# Arduino_Micro_DRAM_Tester.net
KiCad netlist of a schematic drawn in EAGLE
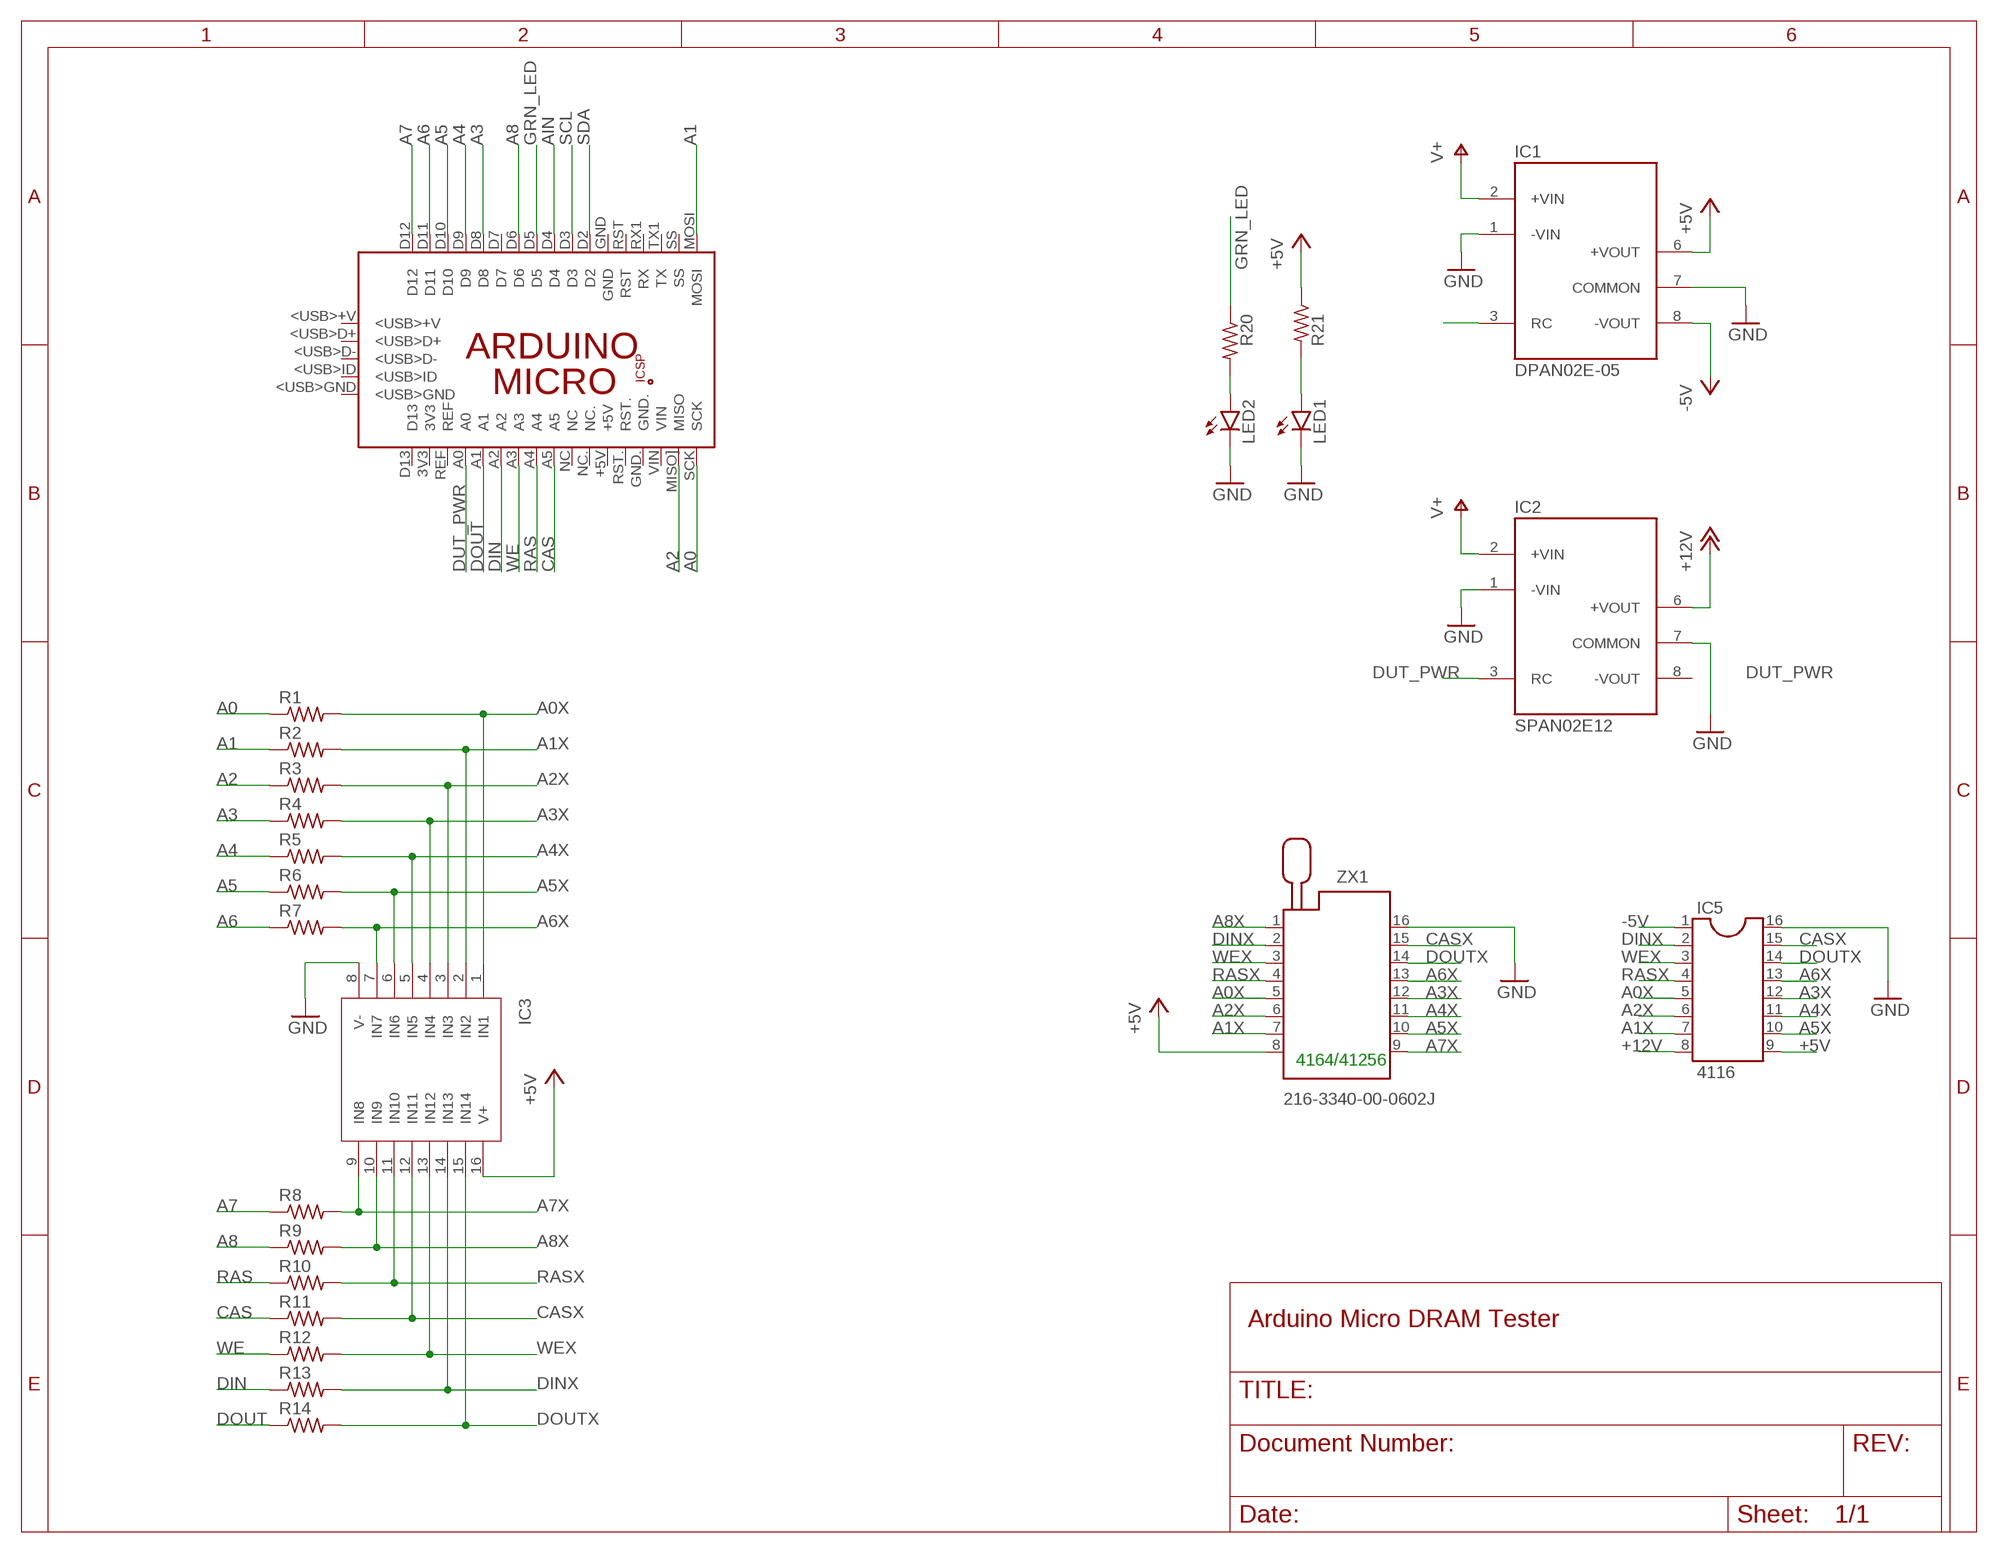
[diagram p0: schematic, sheet 1]

(export (version "E")
  (design (tool "Eeschema 10.0.6"))
  (components
    (comp (ref "IC1")
      (value "DPAN02E-05")
      (footprint "eagle-import:SIP7")
      (libsource (lib "eagle-import") (part "DPAN02"))
    )
    (comp (ref "IC2")
      (value "SPAN02E12")
      (footprint "eagle-import:SIP7")
      (libsource (lib "eagle-import") (part "DPAN02"))
    )
    (comp (ref "IC3")
      (value "SP720")
      (footprint "eagle-import:DIL16")
      (libsource (lib "eagle-import") (part "SP720"))
    )
    (comp (ref "IC5")
      (value "4116")
      (footprint "eagle-import:SOCKET-16")
      (libsource (lib "eagle-import") (part "DIL16S"))
    )
    (comp (ref "LED1")
      (value "LED5MM")
      (footprint "eagle-import:LED5MM")
      (libsource (lib "eagle-import") (part "LED5MM"))
    )
    (comp (ref "LED2")
      (value "LED5MM")
      (footprint "eagle-import:LED5MM")
      (libsource (lib "eagle-import") (part "LED5MM"))
    )
    (comp (ref "PCB1")
      (value "ARDUINO_MICRO")
      (footprint "eagle-import:ARDUINO_MICRO")
      (libsource (lib "eagle-import") (part "ARDUINO_MICRO"))
    )
    (comp (ref "R1")
      (value "R-US_V235/17")
      (footprint "eagle-import:V235_17")
      (libsource (lib "eagle-import") (part "R-US_V235/17"))
    )
    (comp (ref "R2")
      (value "R-US_V235/17")
      (footprint "eagle-import:V235_17")
      (libsource (lib "eagle-import") (part "R-US_V235/17"))
    )
    (comp (ref "R3")
      (value "R-US_V235/17")
      (footprint "eagle-import:V235_17")
      (libsource (lib "eagle-import") (part "R-US_V235/17"))
    )
    (comp (ref "R4")
      (value "R-US_V235/17")
      (footprint "eagle-import:V235_17")
      (libsource (lib "eagle-import") (part "R-US_V235/17"))
    )
    (comp (ref "R5")
      (value "R-US_V235/17")
      (footprint "eagle-import:V235_17")
      (libsource (lib "eagle-import") (part "R-US_V235/17"))
    )
    (comp (ref "R6")
      (value "R-US_V235/17")
      (footprint "eagle-import:V235_17")
      (libsource (lib "eagle-import") (part "R-US_V235/17"))
    )
    (comp (ref "R7")
      (value "R-US_V235/17")
      (footprint "eagle-import:V235_17")
      (libsource (lib "eagle-import") (part "R-US_V235/17"))
    )
    (comp (ref "R8")
      (value "R-US_V235/17")
      (footprint "eagle-import:V235_17")
      (libsource (lib "eagle-import") (part "R-US_V235/17"))
    )
    (comp (ref "R9")
      (value "R-US_V235/17")
      (footprint "eagle-import:V235_17")
      (libsource (lib "eagle-import") (part "R-US_V235/17"))
    )
    (comp (ref "R10")
      (value "R-US_V235/17")
      (footprint "eagle-import:V235_17")
      (libsource (lib "eagle-import") (part "R-US_V235/17"))
    )
    (comp (ref "R11")
      (value "R-US_V235/17")
      (footprint "eagle-import:V235_17")
      (libsource (lib "eagle-import") (part "R-US_V235/17"))
    )
    (comp (ref "R12")
      (value "R-US_V235/17")
      (footprint "eagle-import:V235_17")
      (libsource (lib "eagle-import") (part "R-US_V235/17"))
    )
    (comp (ref "R13")
      (value "R-US_V235/17")
      (footprint "eagle-import:V235_17")
      (libsource (lib "eagle-import") (part "R-US_V235/17"))
    )
    (comp (ref "R14")
      (value "R-US_V235/17")
      (footprint "eagle-import:V235_17")
      (libsource (lib "eagle-import") (part "R-US_V235/17"))
    )
    (comp (ref "R20")
      (value "R-US_0309/10")
      (footprint "eagle-import:0309_10")
      (libsource (lib "eagle-import") (part "resistor_348_R-US_0309/10"))
    )
    (comp (ref "R21")
      (value "R-US_0309/10")
      (footprint "eagle-import:0309_10")
      (libsource (lib "eagle-import") (part "resistor_348_R-US_0309/10"))
    )
    (comp (ref "ZX1")
      (value "216-3340-00-0602J")
      (footprint "eagle-import:216-3340-00-0602J")
      (libsource (lib "eagle-import") (part "216-3340-00-0602J"))
    )
  )
  (nets
    (net (code "1") (name "+5V") (class "Default")
      (node (ref "IC1") (pin "6") (pinfunction "+VOUT_6") (pintype "passive"))
      (node (ref "IC3") (pin "16") (pinfunction "V+_16") (pintype "input"))
      (node (ref "IC5") (pin "9") (pinfunction "9_9") (pintype "passive"))
      (node (ref "R21") (pin "1") (pinfunction "1_1") (pintype "passive"))
      (node (ref "ZX1") (pin "8") (pinfunction "8_8") (pintype "passive"))
    )
    (net (code "2") (name "+12V") (class "Default")
      (node (ref "IC2") (pin "6") (pinfunction "+VOUT_6") (pintype "passive"))
      (node (ref "IC5") (pin "8") (pinfunction "8_8") (pintype "passive"))
    )
    (net (code "3") (name "-5V") (class "Default")
      (node (ref "IC1") (pin "8") (pinfunction "-VOUT_8") (pintype "passive"))
      (node (ref "IC5") (pin "1") (pinfunction "1_1") (pintype "passive"))
    )
    (net (code "4") (name "/A0") (class "Default")
      (node (ref "PCB1") (pin "SCK") (pinfunction "SCK_SCK") (pintype "bidirectional"))
      (node (ref "R1") (pin "1") (pinfunction "1_1") (pintype "passive"))
    )
    (net (code "5") (name "/A0X") (class "Default")
      (node (ref "IC3") (pin "1") (pinfunction "IN1_1") (pintype "input"))
      (node (ref "IC5") (pin "5") (pinfunction "5_5") (pintype "passive"))
      (node (ref "R1") (pin "2") (pinfunction "2_2") (pintype "passive"))
      (node (ref "ZX1") (pin "5") (pinfunction "5_5") (pintype "passive"))
    )
    (net (code "6") (name "/A1") (class "Default")
      (node (ref "PCB1") (pin "MOSI") (pinfunction "MOSI_MOSI") (pintype "bidirectional"))
      (node (ref "R2") (pin "1") (pinfunction "1_1") (pintype "passive"))
    )
    (net (code "7") (name "/A1X") (class "Default")
      (node (ref "IC3") (pin "2") (pinfunction "IN2_2") (pintype "input"))
      (node (ref "IC5") (pin "7") (pinfunction "7_7") (pintype "passive"))
      (node (ref "R2") (pin "2") (pinfunction "2_2") (pintype "passive"))
      (node (ref "ZX1") (pin "7") (pinfunction "7_7") (pintype "passive"))
    )
    (net (code "8") (name "/A2") (class "Default")
      (node (ref "PCB1") (pin "MISO]") (pinfunction "MISO_MISO]") (pintype "bidirectional"))
      (node (ref "R3") (pin "1") (pinfunction "1_1") (pintype "passive"))
    )
    (net (code "9") (name "/A2X") (class "Default")
      (node (ref "IC3") (pin "3") (pinfunction "IN3_3") (pintype "input"))
      (node (ref "IC5") (pin "6") (pinfunction "6_6") (pintype "passive"))
      (node (ref "R3") (pin "2") (pinfunction "2_2") (pintype "passive"))
      (node (ref "ZX1") (pin "6") (pinfunction "6_6") (pintype "passive"))
    )
    (net (code "10") (name "/A3") (class "Default")
      (node (ref "PCB1") (pin "D8") (pinfunction "D8_D8") (pintype "bidirectional"))
      (node (ref "R4") (pin "1") (pinfunction "1_1") (pintype "passive"))
    )
    (net (code "11") (name "/A3X") (class "Default")
      (node (ref "IC3") (pin "4") (pinfunction "IN4_4") (pintype "input"))
      (node (ref "IC5") (pin "12") (pinfunction "12_12") (pintype "passive"))
      (node (ref "R4") (pin "2") (pinfunction "2_2") (pintype "passive"))
      (node (ref "ZX1") (pin "12") (pinfunction "12_12") (pintype "passive"))
    )
    (net (code "12") (name "/A4") (class "Default")
      (node (ref "PCB1") (pin "D9") (pinfunction "D9_D9") (pintype "bidirectional"))
      (node (ref "R5") (pin "1") (pinfunction "1_1") (pintype "passive"))
    )
    (net (code "13") (name "/A4X") (class "Default")
      (node (ref "IC3") (pin "5") (pinfunction "IN5_5") (pintype "input"))
      (node (ref "IC5") (pin "11") (pinfunction "11_11") (pintype "passive"))
      (node (ref "R5") (pin "2") (pinfunction "2_2") (pintype "passive"))
      (node (ref "ZX1") (pin "11") (pinfunction "11_11") (pintype "passive"))
    )
    (net (code "14") (name "/A5") (class "Default")
      (node (ref "PCB1") (pin "D10") (pinfunction "D10_D10") (pintype "bidirectional"))
      (node (ref "R6") (pin "1") (pinfunction "1_1") (pintype "passive"))
    )
    (net (code "15") (name "/A5X") (class "Default")
      (node (ref "IC3") (pin "6") (pinfunction "IN6_6") (pintype "input"))
      (node (ref "IC5") (pin "10") (pinfunction "10_10") (pintype "passive"))
      (node (ref "R6") (pin "2") (pinfunction "2_2") (pintype "passive"))
      (node (ref "ZX1") (pin "10") (pinfunction "10_10") (pintype "passive"))
    )
    (net (code "16") (name "/A6") (class "Default")
      (node (ref "PCB1") (pin "D11") (pinfunction "D11_D11") (pintype "bidirectional"))
      (node (ref "R7") (pin "1") (pinfunction "1_1") (pintype "passive"))
    )
    (net (code "17") (name "/A6X") (class "Default")
      (node (ref "IC3") (pin "7") (pinfunction "IN7_7") (pintype "input"))
      (node (ref "IC5") (pin "13") (pinfunction "13_13") (pintype "passive"))
      (node (ref "R7") (pin "2") (pinfunction "2_2") (pintype "passive"))
      (node (ref "ZX1") (pin "13") (pinfunction "13_13") (pintype "passive"))
    )
    (net (code "18") (name "/A7") (class "Default")
      (node (ref "PCB1") (pin "D12") (pinfunction "D12_D12") (pintype "bidirectional"))
      (node (ref "R8") (pin "1") (pinfunction "1_1") (pintype "passive"))
    )
    (net (code "19") (name "/A7X") (class "Default")
      (node (ref "IC3") (pin "9") (pinfunction "IN8_9") (pintype "input"))
      (node (ref "R8") (pin "2") (pinfunction "2_2") (pintype "passive"))
      (node (ref "ZX1") (pin "9") (pinfunction "9_9") (pintype "passive"))
    )
    (net (code "20") (name "/A8") (class "Default")
      (node (ref "PCB1") (pin "D6") (pinfunction "D6_D6") (pintype "bidirectional"))
      (node (ref "R9") (pin "1") (pinfunction "1_1") (pintype "passive"))
    )
    (net (code "21") (name "/A8X") (class "Default")
      (node (ref "IC3") (pin "10") (pinfunction "IN9_10") (pintype "input"))
      (node (ref "R9") (pin "2") (pinfunction "2_2") (pintype "passive"))
      (node (ref "ZX1") (pin "1") (pinfunction "1_1") (pintype "passive"))
    )
    (net (code "22") (name "/AIN") (class "Default")
      (node (ref "PCB1") (pin "D4") (pinfunction "D4_D4") (pintype "bidirectional"))
    )
    (net (code "23") (name "/CAS") (class "Default")
      (node (ref "PCB1") (pin "A5") (pinfunction "A5_A5") (pintype "bidirectional"))
      (node (ref "R11") (pin "1") (pinfunction "1_1") (pintype "passive"))
    )
    (net (code "24") (name "/CASX") (class "Default")
      (node (ref "IC3") (pin "12") (pinfunction "IN11_12") (pintype "input"))
      (node (ref "IC5") (pin "15") (pinfunction "15_15") (pintype "passive"))
      (node (ref "R11") (pin "2") (pinfunction "2_2") (pintype "passive"))
      (node (ref "ZX1") (pin "15") (pinfunction "15_15") (pintype "passive"))
    )
    (net (code "25") (name "/DIN") (class "Default")
      (node (ref "PCB1") (pin "A2") (pinfunction "A2_A2") (pintype "bidirectional"))
      (node (ref "R13") (pin "1") (pinfunction "1_1") (pintype "passive"))
    )
    (net (code "26") (name "/DINX") (class "Default")
      (node (ref "IC3") (pin "14") (pinfunction "IN13_14") (pintype "input"))
      (node (ref "IC5") (pin "2") (pinfunction "2_2") (pintype "passive"))
      (node (ref "R13") (pin "2") (pinfunction "2_2") (pintype "passive"))
      (node (ref "ZX1") (pin "2") (pinfunction "2_2") (pintype "passive"))
    )
    (net (code "27") (name "/DOUT") (class "Default")
      (node (ref "PCB1") (pin "A1") (pinfunction "A1_A1") (pintype "bidirectional"))
      (node (ref "R14") (pin "1") (pinfunction "1_1") (pintype "passive"))
    )
    (net (code "28") (name "/DOUTX") (class "Default")
      (node (ref "IC3") (pin "15") (pinfunction "IN14_15") (pintype "input"))
      (node (ref "IC5") (pin "14") (pinfunction "14_14") (pintype "passive"))
      (node (ref "R14") (pin "2") (pinfunction "2_2") (pintype "passive"))
      (node (ref "ZX1") (pin "14") (pinfunction "14_14") (pintype "passive"))
    )
    (net (code "29") (name "/DUT_PWR") (class "Default")
      (node (ref "IC1") (pin "3") (pinfunction "RC_3") (pintype "input"))
      (node (ref "IC2") (pin "3") (pinfunction "RC_3") (pintype "input"))
      (node (ref "PCB1") (pin "A0") (pinfunction "A0_A0") (pintype "bidirectional"))
    )
    (net (code "30") (name "/GRN_LED") (class "Default")
      (node (ref "PCB1") (pin "D5") (pinfunction "D5_D5") (pintype "bidirectional"))
      (node (ref "R20") (pin "1") (pinfunction "1_1") (pintype "passive"))
    )
    (net (code "31") (name "/RAS") (class "Default")
      (node (ref "PCB1") (pin "A4") (pinfunction "A4_A4") (pintype "bidirectional"))
      (node (ref "R10") (pin "1") (pinfunction "1_1") (pintype "passive"))
    )
    (net (code "32") (name "/RASX") (class "Default")
      (node (ref "IC3") (pin "11") (pinfunction "IN10_11") (pintype "input"))
      (node (ref "IC5") (pin "4") (pinfunction "4_4") (pintype "passive"))
      (node (ref "R10") (pin "2") (pinfunction "2_2") (pintype "passive"))
      (node (ref "ZX1") (pin "4") (pinfunction "4_4") (pintype "passive"))
    )
    (net (code "33") (name "/SCL") (class "Default")
      (node (ref "PCB1") (pin "D3") (pinfunction "D3_D3") (pintype "bidirectional"))
    )
    (net (code "34") (name "/SDA") (class "Default")
      (node (ref "PCB1") (pin "D2") (pinfunction "D2_D2") (pintype "bidirectional"))
    )
    (net (code "35") (name "/WE") (class "Default")
      (node (ref "PCB1") (pin "A3") (pinfunction "A3_A3") (pintype "bidirectional"))
      (node (ref "R12") (pin "1") (pinfunction "1_1") (pintype "passive"))
    )
    (net (code "36") (name "/WEX") (class "Default")
      (node (ref "IC3") (pin "13") (pinfunction "IN12_13") (pintype "input"))
      (node (ref "IC5") (pin "3") (pinfunction "3_3") (pintype "passive"))
      (node (ref "R12") (pin "2") (pinfunction "2_2") (pintype "passive"))
      (node (ref "ZX1") (pin "3") (pinfunction "3_3") (pintype "passive"))
    )
    (net (code "37") (name "GND") (class "Default")
      (node (ref "IC1") (pin "1") (pinfunction "-VIN_1") (pintype "input"))
      (node (ref "IC1") (pin "7") (pinfunction "COMMON_7") (pintype "passive"))
      (node (ref "IC2") (pin "1") (pinfunction "-VIN_1") (pintype "input"))
      (node (ref "IC2") (pin "7") (pinfunction "COMMON_7") (pintype "passive"))
      (node (ref "IC3") (pin "8") (pinfunction "V-_8") (pintype "input"))
      (node (ref "IC5") (pin "16") (pinfunction "16_16") (pintype "passive"))
      (node (ref "LED1") (pin "K") (pinfunction "C_K") (pintype "passive"))
      (node (ref "LED2") (pin "K") (pinfunction "C_K") (pintype "passive"))
      (node (ref "ZX1") (pin "16") (pinfunction "16_16") (pintype "passive"))
    )
    (net (code "38") (name "Net-(LED1-PadA)") (class "Default")
      (node (ref "LED1") (pin "A") (pinfunction "A_A") (pintype "passive"))
      (node (ref "R21") (pin "2") (pinfunction "2_2") (pintype "passive"))
    )
    (net (code "39") (name "Net-(LED2-PadA)") (class "Default")
      (node (ref "LED2") (pin "A") (pinfunction "A_A") (pintype "passive"))
      (node (ref "R20") (pin "2") (pinfunction "2_2") (pintype "passive"))
    )
    (net (code "40") (name "V+") (class "Default")
      (node (ref "IC1") (pin "2") (pinfunction "+VIN_2") (pintype "input"))
      (node (ref "IC2") (pin "2") (pinfunction "+VIN_2") (pintype "input"))
    )
    (net (code "41") (name "unconnected-(IC2--VOUT-Pad8)") (class "Default")
      (node (ref "IC2") (pin "8") (pinfunction "-VOUT_8") (pintype "passive"))
    )
    (net (code "42") (name "unconnected-(PCB1-Pad+5V)") (class "Default")
      (node (ref "PCB1") (pin "+5V") (pinfunction "+5V_+5V") (pintype "bidirectional"))
    )
    (net (code "43") (name "unconnected-(PCB1-Pad3V3)") (class "Default")
      (node (ref "PCB1") (pin "3V3") (pinfunction "3V3_3V3") (pintype "bidirectional"))
    )
    (net (code "44") (name "unconnected-(PCB1-Pad5V)") (class "Default")
      (node (ref "PCB1") (pin "5V") (pinfunction "5V_5V") (pintype "bidirectional"))
    )
    (net (code "45") (name "unconnected-(PCB1-Pad<USB>+V)") (class "Default")
      (node (ref "PCB1") (pin "<USB>+V") (pinfunction "<USB>+V_<USB>+V") (pintype "bidirectional"))
    )
    (net (code "46") (name "unconnected-(PCB1-Pad<USB>D+)") (class "Default")
      (node (ref "PCB1") (pin "<USB>D+") (pinfunction "<USB>D+_<USB>D+") (pintype "bidirectional"))
    )
    (net (code "47") (name "unconnected-(PCB1-Pad<USB>D-)") (class "Default")
      (node (ref "PCB1") (pin "<USB>D-") (pinfunction "<USB>D-_<USB>D-") (pintype "bidirectional"))
    )
    (net (code "48") (name "unconnected-(PCB1-Pad<USB>GND)") (class "Default")
      (node (ref "PCB1") (pin "<USB>GND") (pinfunction "<USB>GND_<USB>GND") (pintype "bidirectional"))
    )
    (net (code "49") (name "unconnected-(PCB1-Pad<USB>ID)") (class "Default")
      (node (ref "PCB1") (pin "<USB>ID") (pinfunction "<USB>ID_<USB>ID") (pintype "bidirectional"))
    )
    (net (code "50") (name "unconnected-(PCB1-PadD7)") (class "Default")
      (node (ref "PCB1") (pin "D7") (pinfunction "D7_D7") (pintype "bidirectional"))
    )
    (net (code "51") (name "unconnected-(PCB1-PadD13)") (class "Default")
      (node (ref "PCB1") (pin "D13") (pinfunction "D13_D13") (pintype "bidirectional"))
    )
    (net (code "52") (name "unconnected-(PCB1-PadGND)") (class "Default")
      (node (ref "PCB1") (pin "GND") (pinfunction "GND_GND") (pintype "bidirectional"))
    )
    (net (code "53") (name "unconnected-(PCB1-PadGND.)") (class "Default")
      (node (ref "PCB1") (pin "GND.") (pinfunction "GND._GND.") (pintype "bidirectional"))
    )
    (net (code "54") (name "unconnected-(PCB1-PadGND_)") (class "Default")
      (node (ref "PCB1") (pin "GND_") (pinfunction "GND__GND_") (pintype "bidirectional"))
    )
    (net (code "55") (name "unconnected-(PCB1-PadMISO.)") (class "Default")
      (node (ref "PCB1") (pin "MISO.") (pinfunction "MISO._MISO.") (pintype "bidirectional"))
    )
    (net (code "56") (name "unconnected-(PCB1-PadMOSI.)") (class "Default")
      (node (ref "PCB1") (pin "MOSI.") (pinfunction "MOSI._MOSI.") (pintype "bidirectional"))
    )
    (net (code "57") (name "unconnected-(PCB1-PadNC)") (class "Default")
      (node (ref "PCB1") (pin "NC") (pinfunction "NC_NC") (pintype "bidirectional"))
    )
    (net (code "58") (name "unconnected-(PCB1-PadNC.)") (class "Default")
      (node (ref "PCB1") (pin "NC.") (pinfunction "NC._NC.") (pintype "bidirectional"))
    )
    (net (code "59") (name "unconnected-(PCB1-PadREF)") (class "Default")
      (node (ref "PCB1") (pin "REF") (pinfunction "REF_REF") (pintype "bidirectional"))
    )
    (net (code "60") (name "unconnected-(PCB1-PadRESET..)") (class "Default")
      (node (ref "PCB1") (pin "RESET..") (pinfunction "RESET.._RESET..") (pintype "bidirectional"))
    )
    (net (code "61") (name "unconnected-(PCB1-PadRST)") (class "Default")
      (node (ref "PCB1") (pin "RST") (pinfunction "RST_RST") (pintype "bidirectional"))
    )
    (net (code "62") (name "unconnected-(PCB1-PadRST.)") (class "Default")
      (node (ref "PCB1") (pin "RST.") (pinfunction "RST._RST.") (pintype "bidirectional"))
    )
    (net (code "63") (name "unconnected-(PCB1-PadSCK.)") (class "Default")
      (node (ref "PCB1") (pin "SCK.") (pinfunction "SCK._SCK.") (pintype "bidirectional"))
    )
    (net (code "64") (name "unconnected-(PCB1-PadSS)") (class "Default")
      (node (ref "PCB1") (pin "SS") (pinfunction "SS_SS") (pintype "bidirectional"))
    )
    (net (code "65") (name "unconnected-(PCB1-PadVIN)") (class "Default")
      (node (ref "PCB1") (pin "VIN") (pinfunction "VIN_VIN") (pintype "bidirectional"))
    )
    (net (code "66") (name "unconnected-(PCB1-RX-PadRX1)") (class "Default")
      (node (ref "PCB1") (pin "RX1") (pinfunction "RX_RX1") (pintype "bidirectional"))
    )
    (net (code "67") (name "unconnected-(PCB1-TX-PadTX1)") (class "Default")
      (node (ref "PCB1") (pin "TX1") (pinfunction "TX_TX1") (pintype "bidirectional"))
    )
  )
)
